# Bias_Regulators_2.net
KiCad netlist of a schematic drawn in Altium Designer
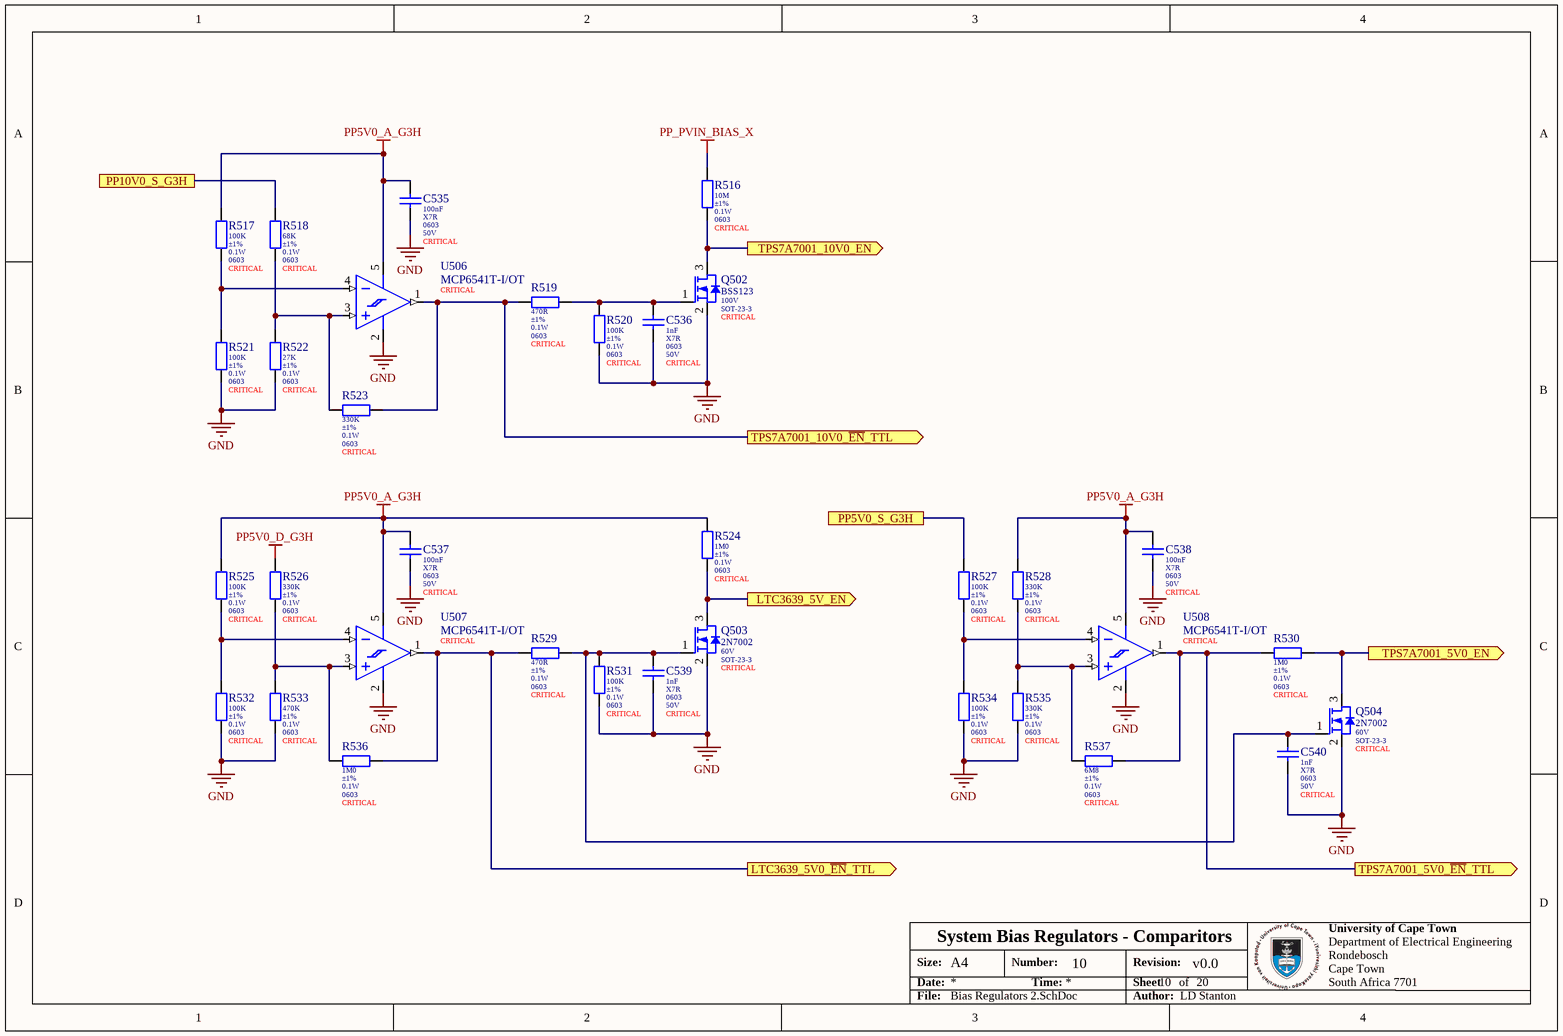
[diagram p0: Bias Regulators 2.SchDoc]

(export (version "E")
  (design (tool "Eeschema 10.0.6"))
  (components
    (comp (ref "C535")
      (value "100nF")
      (footprint "0603 (Yageo DA) B")
      (description "MLCC 100nF 50V 0603 X7R ±10%")
      (fields
        (field (name "DIELECTRIC") "X7R")
        (field (name "PACKAGE") "0603")
        (field (name "VOLTAGE") "50V")
        (field (name "POPULATE") "CRITICAL")
        (field (name "LCSC PART NUMBER") "C14663")
        (field (name "TOLERANCE") "±10%")
      )
      (libsource (lib "University of Cape Town") (part "Symbol"))
    )
    (comp (ref "C536")
      (value "1nF")
      (footprint "0603_080_8 (Samsung) B")
      (description "MLCC 1nF 0603 50V X7R ±10%")
      (fields
        (field (name "DIELECTRIC") "X7R")
        (field (name "PACKAGE") "0603")
        (field (name "VOLTAGE") "50V")
        (field (name "POPULATE") "CRITICAL")
        (field (name "TOLERANCE") "±10%")
        (field (name "LCSC PART NUMBER") "C1588")
      )
      (libsource (lib "University of Cape Town") (part "Symbol"))
    )
    (comp (ref "C537")
      (value "100nF")
      (footprint "0603 (Yageo DA) B")
      (description "MLCC 100nF 50V 0603 X7R ±10%")
      (fields
        (field (name "DIELECTRIC") "X7R")
        (field (name "PACKAGE") "0603")
        (field (name "VOLTAGE") "50V")
        (field (name "POPULATE") "CRITICAL")
        (field (name "LCSC PART NUMBER") "C14663")
        (field (name "TOLERANCE") "±10%")
      )
      (libsource (lib "University of Cape Town") (part "Symbol"))
    )
    (comp (ref "C538")
      (value "100nF")
      (footprint "0603 (Yageo DA) B")
      (description "MLCC 100nF 50V 0603 X7R ±10%")
      (fields
        (field (name "DIELECTRIC") "X7R")
        (field (name "PACKAGE") "0603")
        (field (name "VOLTAGE") "50V")
        (field (name "POPULATE") "CRITICAL")
        (field (name "LCSC PART NUMBER") "C14663")
        (field (name "TOLERANCE") "±10%")
      )
      (libsource (lib "University of Cape Town") (part "Symbol"))
    )
    (comp (ref "C539")
      (value "1nF")
      (footprint "0603_080_8 (Samsung) B")
      (description "MLCC 1nF 0603 50V X7R ±10%")
      (fields
        (field (name "DIELECTRIC") "X7R")
        (field (name "PACKAGE") "0603")
        (field (name "VOLTAGE") "50V")
        (field (name "POPULATE") "CRITICAL")
        (field (name "TOLERANCE") "±10%")
        (field (name "LCSC PART NUMBER") "C1588")
      )
      (libsource (lib "University of Cape Town") (part "Symbol"))
    )
    (comp (ref "C540")
      (value "1nF")
      (footprint "0603_080_8 (Samsung) B")
      (description "MLCC 1nF 0603 50V X7R ±10%")
      (fields
        (field (name "DIELECTRIC") "X7R")
        (field (name "PACKAGE") "0603")
        (field (name "VOLTAGE") "50V")
        (field (name "POPULATE") "CRITICAL")
        (field (name "TOLERANCE") "±10%")
        (field (name "LCSC PART NUMBER") "C1588")
      )
      (libsource (lib "University of Cape Town") (part "Symbol"))
    )
    (comp (ref "Q502")
      (value "BSS123")
      (footprint "SOT-23-3 (2N7002) B")
      (description "Small Signal MOSFET, 170mA, 100V, N-Channel, Enhancement, JCET SOT-23-3")
      (fields
        (field (name "MAXIMUM DRAIN SOURCE VOLTAGE") "100V")
        (field (name "PACKAGE") "SOT-23-3")
        (field (name "PLACEMENT") "CRITICAL")
        (field (name "POWER") "0.35W")
        (field (name "MANUFACTURER") "JCET")
      )
      (libsource (lib "University of Cape Town") (part "N Channel Transistor SOT-23-3"))
    )
    (comp (ref "Q503")
      (value "2N7002")
      (footprint "SOT-23-3 (2N7002) B")
      (description "Small Signal MOSFET, 500 mA, 60 V, N-Channel, Enhancement, JCET SOT-23-3")
      (fields
        (field (name "MAXIMUM DRAIN SOURCE VOLTAGE") "60V")
        (field (name "PACKAGE") "SOT-23-3")
        (field (name "PLACEMENT") "CRITICAL")
        (field (name "LCSC PART NUMBER") "C8545")
        (field (name "MANUFACTURER") "JCET")
      )
      (libsource (lib "University of Cape Town") (part "N Channel Transistor SOT-23-3"))
    )
    (comp (ref "Q504")
      (value "2N7002")
      (footprint "SOT-23-3 (2N7002) B")
      (description "Small Signal MOSFET, 500 mA, 60 V, N-Channel, Enhancement, JCET SOT-23-3")
      (fields
        (field (name "MAXIMUM DRAIN SOURCE VOLTAGE") "60V")
        (field (name "PACKAGE") "SOT-23-3")
        (field (name "PLACEMENT") "CRITICAL")
        (field (name "LCSC PART NUMBER") "C8545")
        (field (name "MANUFACTURER") "JCET")
      )
      (libsource (lib "University of Cape Town") (part "N Channel Transistor SOT-23-3"))
    )
    (comp (ref "R516")
      (value "10M")
      (footprint "0603 (Uniroyal) B")
      (description "Resistor 10M 0603 ±1% Thick Film Uniroyal")
      (fields
        (field (name "TOLERANCE") "±1%")
        (field (name "POWER") "0.1W")
        (field (name "PACKAGE") "0603")
        (field (name "POPULATE") "CRITICAL")
        (field (name "MANUFACTURER") "Uniroyal")
        (field (name "LCSC PART NUMBER") "C7250")
      )
      (libsource (lib "University of Cape Town") (part "Chip Resistor"))
    )
    (comp (ref "R517")
      (value "100K")
      (footprint "0603 (Uniroyal) B")
      (description "Resistor 100K 0603 ±1% Thick Film Uniroyal")
      (fields
        (field (name "TOLERANCE") "±1%")
        (field (name "POWER") "0.1W")
        (field (name "PACKAGE") "0603")
        (field (name "POPULATE") "CRITICAL")
        (field (name "MANUFACTURER") "Uniroyal")
        (field (name "LCSC PART NUMBER") "C25803")
      )
      (libsource (lib "University of Cape Town") (part "Chip Resistor"))
    )
    (comp (ref "R518")
      (value "68K")
      (footprint "0603 (Uniroyal) B")
      (description "Resistor 68K 0603 ±1% Thick Film Uniroyal")
      (fields
        (field (name "TOLERANCE") "±1%")
        (field (name "POWER") "0.1W")
        (field (name "PACKAGE") "0603")
        (field (name "POPULATE") "CRITICAL")
        (field (name "MANUFACTURER") "Uniroyal")
        (field (name "LCSC PART NUMBER") "C23231")
      )
      (libsource (lib "University of Cape Town") (part "Chip Resistor"))
    )
    (comp (ref "R519")
      (value "470R")
      (footprint "0603 (Uniroyal) B")
      (description "Resistor 470R 0603 ±5% Thick Film Uniroyal")
      (fields
        (field (name "TOLERANCE") "±1%")
        (field (name "POWER") "0.1W")
        (field (name "PACKAGE") "0603")
        (field (name "POPULATE") "CRITICAL")
        (field (name "MANUFACTURER") "Uniroyal")
        (field (name "LCSC PART NUMBER") "C23179")
      )
      (libsource (lib "University of Cape Town") (part "Chip Resistor"))
    )
    (comp (ref "R520")
      (value "100K")
      (footprint "0603 (Uniroyal) B")
      (description "Resistor 100K 0603 ±1% Thick Film Uniroyal")
      (fields
        (field (name "TOLERANCE") "±1%")
        (field (name "POWER") "0.1W")
        (field (name "PACKAGE") "0603")
        (field (name "POPULATE") "CRITICAL")
        (field (name "MANUFACTURER") "Uniroyal")
        (field (name "LCSC PART NUMBER") "C25803")
      )
      (libsource (lib "University of Cape Town") (part "Chip Resistor"))
    )
    (comp (ref "R521")
      (value "100K")
      (footprint "0603 (Uniroyal) B")
      (description "Resistor 100K 0603 ±1% Thick Film Uniroyal")
      (fields
        (field (name "TOLERANCE") "±1%")
        (field (name "POWER") "0.1W")
        (field (name "PACKAGE") "0603")
        (field (name "POPULATE") "CRITICAL")
        (field (name "MANUFACTURER") "Uniroyal")
        (field (name "LCSC PART NUMBER") "C25803")
      )
      (libsource (lib "University of Cape Town") (part "Chip Resistor"))
    )
    (comp (ref "R522")
      (value "27K")
      (footprint "0603 (Uniroyal) B")
      (description "Resistor 27K 0603 ±1% Thick Film Uniroyal")
      (fields
        (field (name "TOLERANCE") "±1%")
        (field (name "POWER") "0.1W")
        (field (name "PACKAGE") "0603")
        (field (name "POPULATE") "CRITICAL")
        (field (name "MANUFACTURER") "Uniroyal")
        (field (name "LCSC PART NUMBER") "C22967")
      )
      (libsource (lib "University of Cape Town") (part "Chip Resistor"))
    )
    (comp (ref "R523")
      (value "330K")
      (footprint "0603 (Uniroyal) B")
      (description "Resistor 330K 0603 ±1% Thick Film Uniroyal")
      (fields
        (field (name "TOLERANCE") "±1%")
        (field (name "POWER") "0.1W")
        (field (name "PACKAGE") "0603")
        (field (name "POPULATE") "CRITICAL")
        (field (name "MANUFACTURER") "Uniroyal")
        (field (name "LCSC PART NUMBER") "C23137")
      )
      (libsource (lib "University of Cape Town") (part "Chip Resistor"))
    )
    (comp (ref "R524")
      (value "1M0")
      (footprint "0603 (Uniroyal) B")
      (description "Resistor 1M0 0603 ±1% Thick Film Uniroyal")
      (fields
        (field (name "TOLERANCE") "±1%")
        (field (name "POWER") "0.1W")
        (field (name "PACKAGE") "0603")
        (field (name "POPULATE") "CRITICAL")
        (field (name "MANUFACTURER") "Uniroyal")
        (field (name "LCSC PART NUMBER") "C22935")
      )
      (libsource (lib "University of Cape Town") (part "Chip Resistor"))
    )
    (comp (ref "R525")
      (value "100K")
      (footprint "0603 (Uniroyal) B")
      (description "Resistor 100K 0603 ±1% Thick Film Uniroyal")
      (fields
        (field (name "TOLERANCE") "±1%")
        (field (name "POWER") "0.1W")
        (field (name "PACKAGE") "0603")
        (field (name "POPULATE") "CRITICAL")
        (field (name "MANUFACTURER") "Uniroyal")
        (field (name "LCSC PART NUMBER") "C25803")
      )
      (libsource (lib "University of Cape Town") (part "Chip Resistor"))
    )
    (comp (ref "R526")
      (value "330K")
      (footprint "0603 (Uniroyal) B")
      (description "Resistor 330K 0603 ±1% Thick Film Uniroyal")
      (fields
        (field (name "TOLERANCE") "±1%")
        (field (name "POWER") "0.1W")
        (field (name "PACKAGE") "0603")
        (field (name "POPULATE") "CRITICAL")
        (field (name "MANUFACTURER") "Uniroyal")
        (field (name "LCSC PART NUMBER") "C23137")
      )
      (libsource (lib "University of Cape Town") (part "Chip Resistor"))
    )
    (comp (ref "R527")
      (value "100K")
      (footprint "0603 (Uniroyal) B")
      (description "Resistor 100K 0603 ±1% Thick Film Uniroyal")
      (fields
        (field (name "TOLERANCE") "±1%")
        (field (name "POWER") "0.1W")
        (field (name "PACKAGE") "0603")
        (field (name "POPULATE") "CRITICAL")
        (field (name "MANUFACTURER") "Uniroyal")
        (field (name "LCSC PART NUMBER") "C25803")
      )
      (libsource (lib "University of Cape Town") (part "Chip Resistor"))
    )
    (comp (ref "R528")
      (value "330K")
      (footprint "0603 (Uniroyal) B")
      (description "Resistor 330K 0603 ±1% Thick Film Uniroyal")
      (fields
        (field (name "TOLERANCE") "±1%")
        (field (name "POWER") "0.1W")
        (field (name "PACKAGE") "0603")
        (field (name "POPULATE") "CRITICAL")
        (field (name "MANUFACTURER") "Uniroyal")
        (field (name "LCSC PART NUMBER") "C23137")
      )
      (libsource (lib "University of Cape Town") (part "Chip Resistor"))
    )
    (comp (ref "R529")
      (value "470R")
      (footprint "0603 (Uniroyal) B")
      (description "Resistor 470R 0603 ±5% Thick Film Uniroyal")
      (fields
        (field (name "TOLERANCE") "±1%")
        (field (name "POWER") "0.1W")
        (field (name "PACKAGE") "0603")
        (field (name "POPULATE") "CRITICAL")
        (field (name "MANUFACTURER") "Uniroyal")
        (field (name "LCSC PART NUMBER") "C23179")
      )
      (libsource (lib "University of Cape Town") (part "Chip Resistor"))
    )
    (comp (ref "R530")
      (value "1M0")
      (footprint "0603 (Uniroyal) B")
      (description "Resistor 1M0 0603 ±1% Thick Film Uniroyal")
      (fields
        (field (name "TOLERANCE") "±1%")
        (field (name "POWER") "0.1W")
        (field (name "PACKAGE") "0603")
        (field (name "POPULATE") "CRITICAL")
        (field (name "MANUFACTURER") "Uniroyal")
        (field (name "LCSC PART NUMBER") "C22935")
      )
      (libsource (lib "University of Cape Town") (part "Chip Resistor"))
    )
    (comp (ref "R531")
      (value "100K")
      (footprint "0603 (Uniroyal) B")
      (description "Resistor 100K 0603 ±1% Thick Film Uniroyal")
      (fields
        (field (name "TOLERANCE") "±1%")
        (field (name "POWER") "0.1W")
        (field (name "PACKAGE") "0603")
        (field (name "POPULATE") "CRITICAL")
        (field (name "MANUFACTURER") "Uniroyal")
        (field (name "LCSC PART NUMBER") "C25803")
      )
      (libsource (lib "University of Cape Town") (part "Chip Resistor"))
    )
    (comp (ref "R532")
      (value "100K")
      (footprint "0603 (Uniroyal) B")
      (description "Resistor 100K 0603 ±1% Thick Film Uniroyal")
      (fields
        (field (name "TOLERANCE") "±1%")
        (field (name "POWER") "0.1W")
        (field (name "PACKAGE") "0603")
        (field (name "POPULATE") "CRITICAL")
        (field (name "MANUFACTURER") "Uniroyal")
        (field (name "LCSC PART NUMBER") "C25803")
      )
      (libsource (lib "University of Cape Town") (part "Chip Resistor"))
    )
    (comp (ref "R533")
      (value "470K")
      (footprint "0603 (Uniroyal) B")
      (description "Resistor 470K 0603 ±1% Thick Film Uniroyal")
      (fields
        (field (name "TOLERANCE") "±1%")
        (field (name "POWER") "0.1W")
        (field (name "PACKAGE") "0603")
        (field (name "POPULATE") "CRITICAL")
        (field (name "LCSC PART NUMBER") "C23178")
        (field (name "MANUFACTURER") "Uniroyal")
      )
      (libsource (lib "University of Cape Town") (part "Chip Resistor"))
    )
    (comp (ref "R534")
      (value "100K")
      (footprint "0603 (Uniroyal) B")
      (description "Resistor 100K 0603 ±1% Thick Film Uniroyal")
      (fields
        (field (name "TOLERANCE") "±1%")
        (field (name "POWER") "0.1W")
        (field (name "PACKAGE") "0603")
        (field (name "POPULATE") "CRITICAL")
        (field (name "MANUFACTURER") "Uniroyal")
        (field (name "LCSC PART NUMBER") "C25803")
      )
      (libsource (lib "University of Cape Town") (part "Chip Resistor"))
    )
    (comp (ref "R535")
      (value "330K")
      (footprint "0603 (Uniroyal) B")
      (description "Resistor 330K 0603 ±1% Thick Film Uniroyal")
      (fields
        (field (name "TOLERANCE") "±1%")
        (field (name "POWER") "0.1W")
        (field (name "PACKAGE") "0603")
        (field (name "POPULATE") "CRITICAL")
        (field (name "MANUFACTURER") "Uniroyal")
        (field (name "LCSC PART NUMBER") "C23137")
      )
      (libsource (lib "University of Cape Town") (part "Chip Resistor"))
    )
    (comp (ref "R536")
      (value "1M0")
      (footprint "0603 (Uniroyal) B")
      (description "Resistor 1M0 0603 ±1% Thick Film Uniroyal")
      (fields
        (field (name "TOLERANCE") "±1%")
        (field (name "POWER") "0.1W")
        (field (name "PACKAGE") "0603")
        (field (name "POPULATE") "CRITICAL")
        (field (name "MANUFACTURER") "Uniroyal")
        (field (name "LCSC PART NUMBER") "C22935")
      )
      (libsource (lib "University of Cape Town") (part "Chip Resistor"))
    )
    (comp (ref "R537")
      (value "6M8")
      (footprint "0603 (Uniroyal) B")
      (description "Resistor 6M8 0603 ±1% Thick Film Uniroyal")
      (fields
        (field (name "TOLERANCE") "±1%")
        (field (name "POWER") "0.1W")
        (field (name "PACKAGE") "0603")
        (field (name "POPULATE") "CRITICAL")
        (field (name "LCSC PART NUMBER") "C23213")
        (field (name "MANUFACTURER") "Uniroyal")
      )
      (libsource (lib "University of Cape Town") (part "Chip Resistor"))
    )
    (comp (ref "U506")
      (value "MCP6541T-I/OT")
      (footprint "SOT-23-5 (MCP75x) B")
      (description "Comparator, Push-Pull, 1V6-5V5, 600nA,  SOT-23-5")
      (fields (field (name "PLACEMENT") "CRITICAL") (field (name "LCSC PART NUMBER") "C80839"))
      (libsource (lib "University of Cape Town") (part "MCP7541"))
    )
    (comp (ref "U507")
      (value "MCP6541T-I/OT")
      (footprint "SOT-23-5 (MCP75x) B")
      (description "Comparator, Push-Pull, 1V6-5V5, 600nA,  SOT-23-5")
      (fields (field (name "PLACEMENT") "CRITICAL") (field (name "LCSC PART NUMBER") "C80839"))
      (libsource (lib "University of Cape Town") (part "MCP7541"))
    )
    (comp (ref "U508")
      (value "MCP6541T-I/OT")
      (footprint "SOT-23-5 (MCP75x) B")
      (description "Comparator, Push-Pull, 1V6-5V5, 600nA,  SOT-23-5")
      (fields (field (name "PLACEMENT") "CRITICAL") (field (name "LCSC PART NUMBER") "C80839"))
      (libsource (lib "University of Cape Town") (part "MCP7541"))
    )
  )
  (nets
    (net (code "1") (name "/LTC3639_5V0_~{EN}_TTL") (class "Default")
      (node (ref "R529") (pin "1") (pinfunction "1_1") (pintype "passive"))
      (node (ref "R536") (pin "2") (pinfunction "2_2") (pintype "passive"))
      (node (ref "U507") (pin "1") (pinfunction "OUT_1") (pintype "output"))
    )
    (net (code "2") (name "/LTC3639_5V_EN") (class "Default")
      (node (ref "Q503") (pin "3") (pinfunction "D_3") (pintype "passive"))
      (node (ref "R524") (pin "2") (pinfunction "2_2") (pintype "passive"))
    )
    (net (code "3") (name "/PP5V0_S_G3H") (class "Default")
      (node (ref "R527") (pin "1") (pinfunction "1_1") (pintype "passive"))
    )
    (net (code "4") (name "/PP10V0_S_G3H") (class "Default")
      (node (ref "R518") (pin "1") (pinfunction "1_1") (pintype "passive"))
    )
    (net (code "5") (name "/TPS7A7001_5V0_EN") (class "Default")
      (node (ref "Q504") (pin "3") (pinfunction "D_3") (pintype "passive"))
      (node (ref "R530") (pin "2") (pinfunction "2_2") (pintype "passive"))
    )
    (net (code "6") (name "/TPS7A7001_5V0_~{EN}_TTL") (class "Default")
      (node (ref "R530") (pin "1") (pinfunction "1_1") (pintype "passive"))
      (node (ref "R537") (pin "2") (pinfunction "2_2") (pintype "passive"))
      (node (ref "U508") (pin "1") (pinfunction "OUT_1") (pintype "output"))
    )
    (net (code "7") (name "/TPS7A7001_10V0_EN") (class "Default")
      (node (ref "Q502") (pin "3") (pinfunction "D_3") (pintype "passive"))
      (node (ref "R516") (pin "2") (pinfunction "2_2") (pintype "passive"))
    )
    (net (code "8") (name "/TPS7A7001_10V0_~{EN}_TTL") (class "Default")
      (node (ref "R519") (pin "1") (pinfunction "1_1") (pintype "passive"))
      (node (ref "R523") (pin "2") (pinfunction "2_2") (pintype "passive"))
      (node (ref "U506") (pin "1") (pinfunction "OUT_1") (pintype "output"))
    )
    (net (code "9") (name "GND") (class "Default")
      (node (ref "C535") (pin "2") (pinfunction "2_2") (pintype "passive"))
      (node (ref "C536") (pin "2") (pinfunction "2_2") (pintype "passive"))
      (node (ref "C537") (pin "2") (pinfunction "2_2") (pintype "passive"))
      (node (ref "C538") (pin "2") (pinfunction "2_2") (pintype "passive"))
      (node (ref "C539") (pin "2") (pinfunction "2_2") (pintype "passive"))
      (node (ref "C540") (pin "2") (pinfunction "2_2") (pintype "passive"))
      (node (ref "Q502") (pin "2") (pinfunction "S_2") (pintype "passive"))
      (node (ref "Q503") (pin "2") (pinfunction "S_2") (pintype "passive"))
      (node (ref "Q504") (pin "2") (pinfunction "S_2") (pintype "passive"))
      (node (ref "R520") (pin "2") (pinfunction "2_2") (pintype "passive"))
      (node (ref "R521") (pin "2") (pinfunction "2_2") (pintype "passive"))
      (node (ref "R522") (pin "2") (pinfunction "2_2") (pintype "passive"))
      (node (ref "R531") (pin "2") (pinfunction "2_2") (pintype "passive"))
      (node (ref "R532") (pin "2") (pinfunction "2_2") (pintype "passive"))
      (node (ref "R533") (pin "2") (pinfunction "2_2") (pintype "passive"))
      (node (ref "R534") (pin "2") (pinfunction "2_2") (pintype "passive"))
      (node (ref "R535") (pin "2") (pinfunction "2_2") (pintype "passive"))
      (node (ref "U506") (pin "2") (pinfunction "VSS_2") (pintype "power_in"))
      (node (ref "U507") (pin "2") (pinfunction "VSS_2") (pintype "power_in"))
      (node (ref "U508") (pin "2") (pinfunction "VSS_2") (pintype "power_in"))
    )
    (net (code "10") (name "Net-(Q502-G)") (class "Default")
      (node (ref "C536") (pin "1") (pinfunction "1_1") (pintype "passive"))
      (node (ref "Q502") (pin "1") (pinfunction "G_1") (pintype "passive"))
      (node (ref "R519") (pin "2") (pinfunction "2_2") (pintype "passive"))
      (node (ref "R520") (pin "1") (pinfunction "1_1") (pintype "passive"))
    )
    (net (code "11") (name "Net-(Q503-G)") (class "Default")
      (node (ref "C539") (pin "1") (pinfunction "1_1") (pintype "passive"))
      (node (ref "C540") (pin "1") (pinfunction "1_1") (pintype "passive"))
      (node (ref "Q503") (pin "1") (pinfunction "G_1") (pintype "passive"))
      (node (ref "Q504") (pin "1") (pinfunction "G_1") (pintype "passive"))
      (node (ref "R529") (pin "2") (pinfunction "2_2") (pintype "passive"))
      (node (ref "R531") (pin "1") (pinfunction "1_1") (pintype "passive"))
    )
    (net (code "12") (name "Net-(U506-VIN+)") (class "Default")
      (node (ref "R518") (pin "2") (pinfunction "2_2") (pintype "passive"))
      (node (ref "R522") (pin "1") (pinfunction "1_1") (pintype "passive"))
      (node (ref "R523") (pin "1") (pinfunction "1_1") (pintype "passive"))
      (node (ref "U506") (pin "3") (pinfunction "VIN+_3") (pintype "input"))
    )
    (net (code "13") (name "Net-(U506-VIN-)") (class "Default")
      (node (ref "R517") (pin "2") (pinfunction "2_2") (pintype "passive"))
      (node (ref "R521") (pin "1") (pinfunction "1_1") (pintype "passive"))
      (node (ref "U506") (pin "4") (pinfunction "VIN-_4") (pintype "input"))
    )
    (net (code "14") (name "Net-(U507-VIN+)") (class "Default")
      (node (ref "R526") (pin "2") (pinfunction "2_2") (pintype "passive"))
      (node (ref "R533") (pin "1") (pinfunction "1_1") (pintype "passive"))
      (node (ref "R536") (pin "1") (pinfunction "1_1") (pintype "passive"))
      (node (ref "U507") (pin "3") (pinfunction "VIN+_3") (pintype "input"))
    )
    (net (code "15") (name "Net-(U507-VIN-)") (class "Default")
      (node (ref "R525") (pin "2") (pinfunction "2_2") (pintype "passive"))
      (node (ref "R532") (pin "1") (pinfunction "1_1") (pintype "passive"))
      (node (ref "U507") (pin "4") (pinfunction "VIN-_4") (pintype "input"))
    )
    (net (code "16") (name "Net-(U508-VIN+)") (class "Default")
      (node (ref "R528") (pin "2") (pinfunction "2_2") (pintype "passive"))
      (node (ref "R535") (pin "1") (pinfunction "1_1") (pintype "passive"))
      (node (ref "R537") (pin "1") (pinfunction "1_1") (pintype "passive"))
      (node (ref "U508") (pin "3") (pinfunction "VIN+_3") (pintype "input"))
    )
    (net (code "17") (name "Net-(U508-VIN-)") (class "Default")
      (node (ref "R527") (pin "2") (pinfunction "2_2") (pintype "passive"))
      (node (ref "R534") (pin "1") (pinfunction "1_1") (pintype "passive"))
      (node (ref "U508") (pin "4") (pinfunction "VIN-_4") (pintype "input"))
    )
    (net (code "18") (name "PP5V0_A_G3H") (class "Default")
      (node (ref "C535") (pin "1") (pinfunction "1_1") (pintype "passive"))
      (node (ref "C537") (pin "1") (pinfunction "1_1") (pintype "passive"))
      (node (ref "C538") (pin "1") (pinfunction "1_1") (pintype "passive"))
      (node (ref "R517") (pin "1") (pinfunction "1_1") (pintype "passive"))
      (node (ref "R524") (pin "1") (pinfunction "1_1") (pintype "passive"))
      (node (ref "R525") (pin "1") (pinfunction "1_1") (pintype "passive"))
      (node (ref "R528") (pin "1") (pinfunction "1_1") (pintype "passive"))
      (node (ref "U506") (pin "5") (pinfunction "VDD_5") (pintype "power_in"))
      (node (ref "U507") (pin "5") (pinfunction "VDD_5") (pintype "power_in"))
      (node (ref "U508") (pin "5") (pinfunction "VDD_5") (pintype "power_in"))
    )
    (net (code "19") (name "PP5V0_D_G3H") (class "Default")
      (node (ref "R526") (pin "1") (pinfunction "1_1") (pintype "passive"))
    )
    (net (code "20") (name "PP_PVIN_BIAS_X") (class "Default")
      (node (ref "R516") (pin "1") (pinfunction "1_1") (pintype "passive"))
    )
  )
)
